# rs485_interface.net
KiCad netlist of a schematic drawn in EAGLE
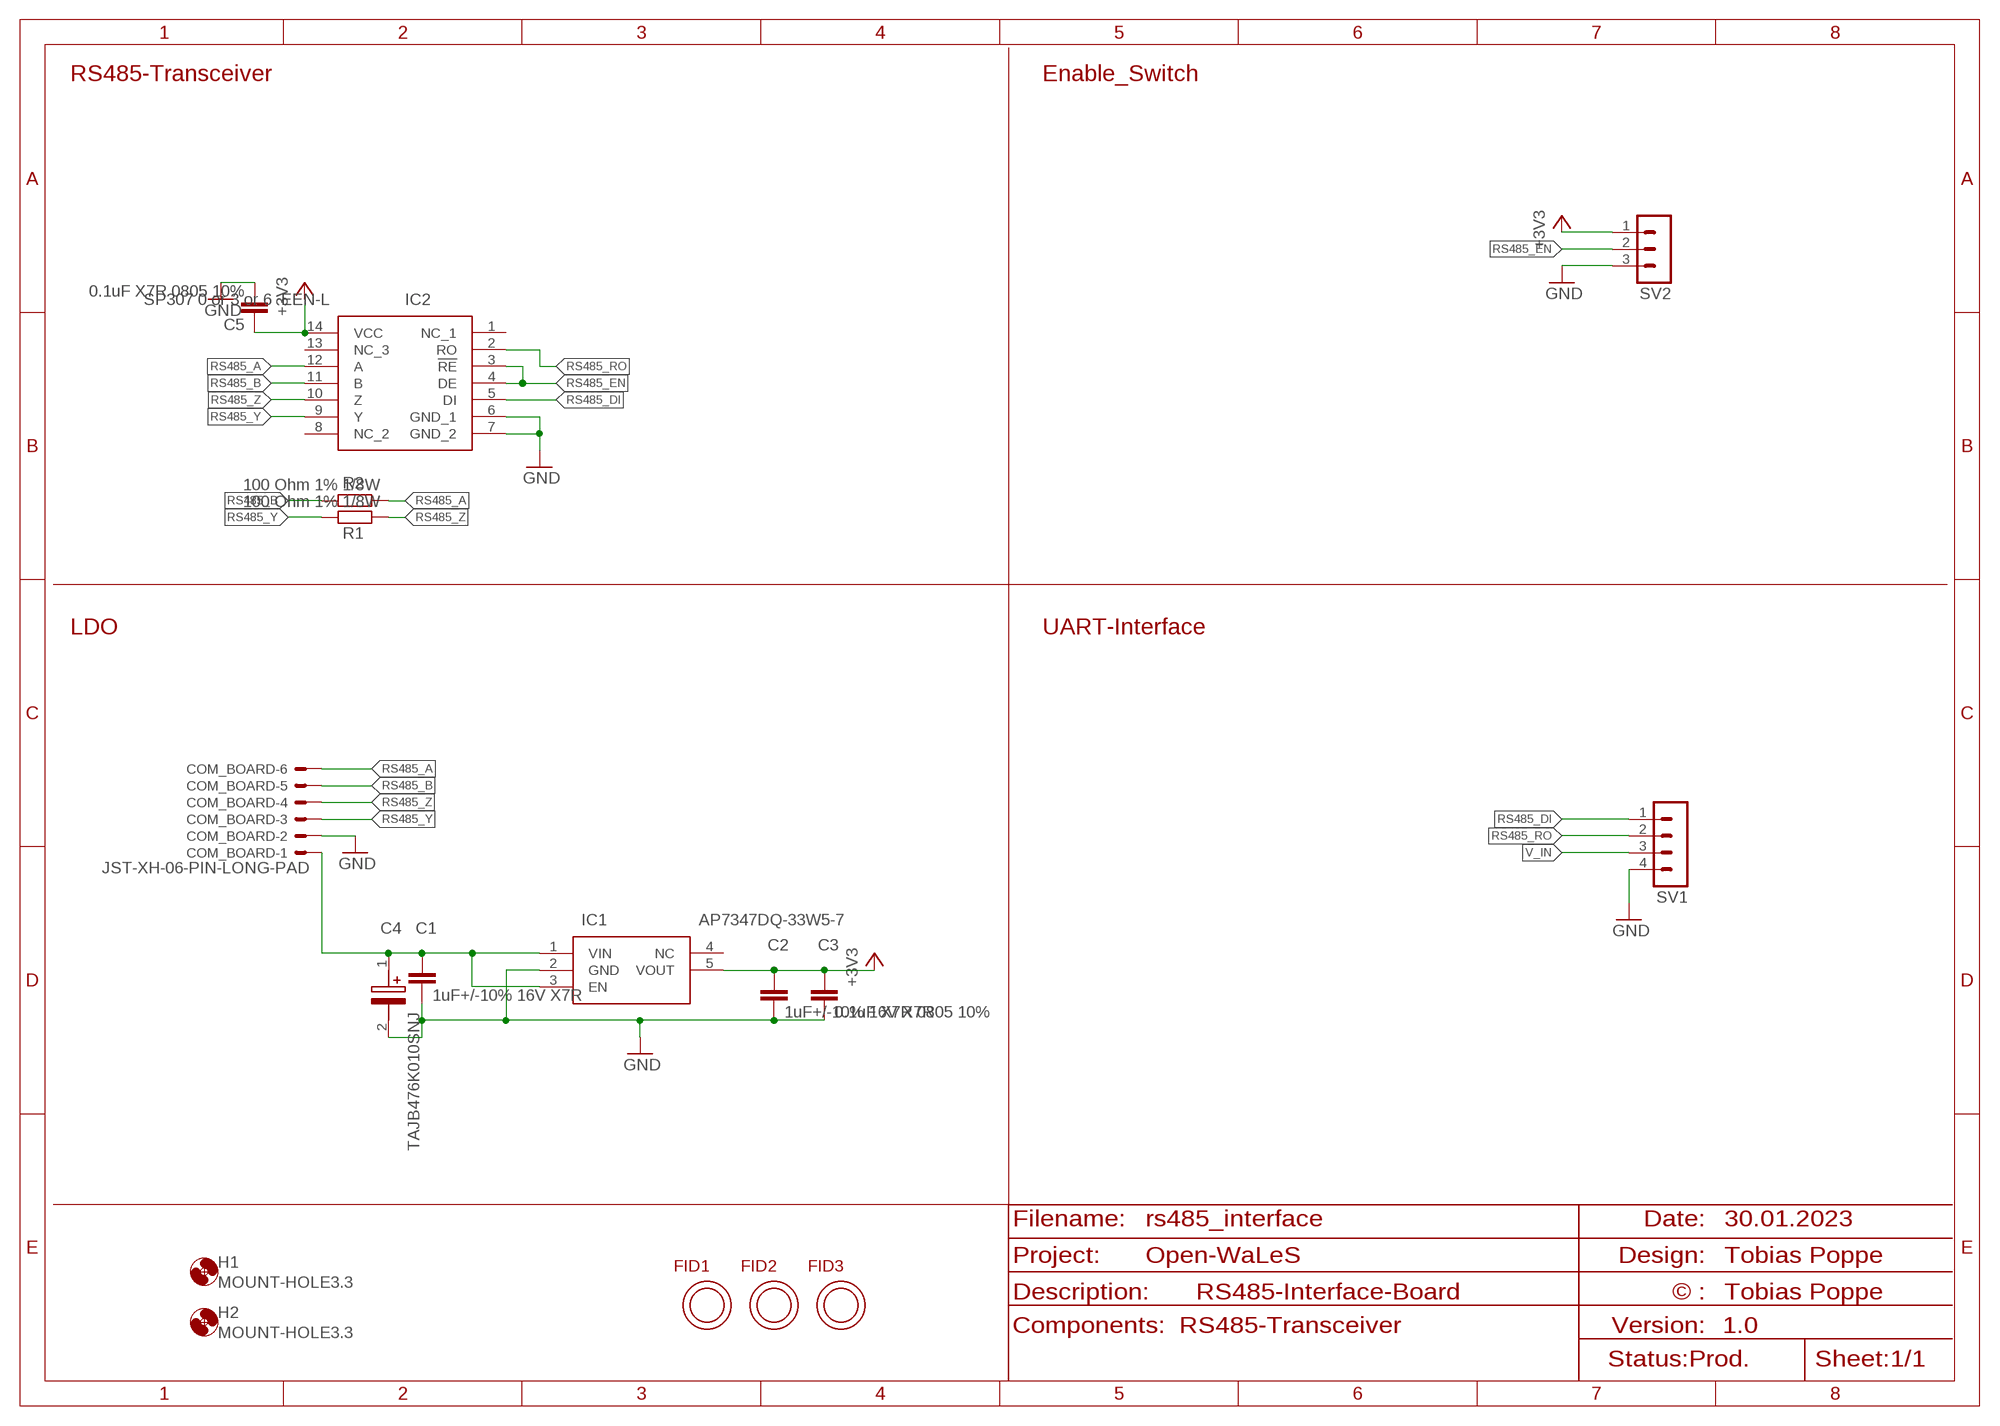
[diagram p0: schematic, sheet 1]

(export (version "E")
  (design (tool "Eeschema 10.0.6"))
  (components
    (comp (ref "C1")
      (value "1uF+/-10% 16V X7R")
      (footprint "eagle-import:C0805")
      (libsource (lib "eagle-import") (part "C-EUC0805"))
    )
    (comp (ref "C2")
      (value "1uF+/-10% 16V X7R")
      (footprint "eagle-import:C0805")
      (libsource (lib "eagle-import") (part "C-EUC0805"))
    )
    (comp (ref "C3")
      (value "0.1uF X7R 0805 10%")
      (footprint "eagle-import:C0805")
      (libsource (lib "eagle-import") (part "C-EUC0805"))
    )
    (comp (ref "C4")
      (value "TAJB476K010SNJ")
      (footprint "eagle-import:CAPPM3528X210N")
      (fields (field (name "MOUSER_PART_NUMBER") "581-TAJB476K010SNJ"))
      (libsource (lib "eagle-import") (part "TAJB476K010SNJ"))
    )
    (comp (ref "C5")
      (value "0.1uF X7R 0805 10%")
      (footprint "eagle-import:C0805")
      (libsource (lib "eagle-import") (part "C-EUC0805"))
    )
    (comp (ref "COM_BOARD")
      (value "JST-XH-06-PIN-LONG-PAD")
      (footprint "eagle-import:JST-XH-06-PACKAGE-LONG-PAD")
      (libsource (lib "eagle-import") (part "JST-XH-06-PIN-LONG-PAD"))
    )
    (comp (ref "FID1")
      (value "OPEN-PNP-FIDUCIAL")
      (footprint "eagle-import:OPEN-PNP-FIDUCIAL")
      (libsource (lib "eagle-import") (part "OPEN-PNP-FIDUCIAL"))
    )
    (comp (ref "FID2")
      (value "OPEN-PNP-FIDUCIAL")
      (footprint "eagle-import:OPEN-PNP-FIDUCIAL")
      (libsource (lib "eagle-import") (part "OPEN-PNP-FIDUCIAL"))
    )
    (comp (ref "FID3")
      (value "OPEN-PNP-FIDUCIAL")
      (footprint "eagle-import:OPEN-PNP-FIDUCIAL")
      (libsource (lib "eagle-import") (part "OPEN-PNP-FIDUCIAL"))
    )
    (comp (ref "H1")
      (value "MOUNT-HOLE3.3")
      (footprint "eagle-import:3,3")
      (libsource (lib "eagle-import") (part "MOUNT-HOLE3.3"))
    )
    (comp (ref "H2")
      (value "MOUNT-HOLE3.3")
      (footprint "eagle-import:3,3")
      (libsource (lib "eagle-import") (part "MOUNT-HOLE3.3"))
    )
    (comp (ref "IC1")
      (value "AP7347DQ-33W5-7")
      (footprint "eagle-import:SOT95P280X145-5N")
      (fields (field (name "MOUSER_PART_NUMBER") "621-AP7347DQ-33W5-7"))
      (libsource (lib "eagle-import") (part "AP7347DQ-33W5-7"))
    )
    (comp (ref "IC2")
      (value "SP307 0 or 3 or 6 EEN-L")
      (footprint "eagle-import:SOIC127P600X175-14N")
      (fields
        (field (name "MANUFACTURER_PART_NUMBER") "SP3076EEN-L")
        (field (name "MOUSER_PART_NUMBER") "701-SP3076EEN-L")
      )
      (libsource (lib "eagle-import") (part "SP3076EEN-L"))
    )
    (comp (ref "R1")
      (value "100 Ohm 1% 1/8W")
      (footprint "eagle-import:R0805")
      (libsource (lib "eagle-import") (part "R-EU_R0805"))
    )
    (comp (ref "R2")
      (value "100 Ohm 1% 1/8W")
      (footprint "eagle-import:R0805")
      (libsource (lib "eagle-import") (part "R-EU_R0805"))
    )
    (comp (ref "SV1")
      (value "MA04-1")
      (footprint "eagle-import:MA04-1")
      (libsource (lib "eagle-import") (part "MA04-1"))
    )
    (comp (ref "SV2")
      (value "MA03-1")
      (footprint "eagle-import:MA03-1")
      (libsource (lib "eagle-import") (part "MA03-1"))
    )
  )
  (nets
    (net (code "1") (name "+3V3") (class "Default")
      (node (ref "C2") (pin "1") (pinfunction "1_1") (pintype "passive"))
      (node (ref "C3") (pin "1") (pinfunction "1_1") (pintype "passive"))
      (node (ref "C5") (pin "1") (pinfunction "1_1") (pintype "passive"))
      (node (ref "IC1") (pin "5") (pinfunction "VOUT_5") (pintype "bidirectional"))
      (node (ref "IC2") (pin "14") (pinfunction "VCC_14") (pintype "bidirectional"))
      (node (ref "SV2") (pin "1") (pinfunction "1_1") (pintype "passive"))
    )
    (net (code "2") (name "GND") (class "Default")
      (node (ref "C1") (pin "2") (pinfunction "2_2") (pintype "passive"))
      (node (ref "C2") (pin "2") (pinfunction "2_2") (pintype "passive"))
      (node (ref "C3") (pin "2") (pinfunction "2_2") (pintype "passive"))
      (node (ref "C4") (pin "2") (pinfunction "-_2") (pintype "bidirectional"))
      (node (ref "C5") (pin "2") (pinfunction "2_2") (pintype "passive"))
      (node (ref "COM_BOARD") (pin "2") (pinfunction "S_2") (pintype "passive"))
      (node (ref "IC1") (pin "2") (pinfunction "GND_2") (pintype "bidirectional"))
      (node (ref "IC2") (pin "6") (pinfunction "GND_1_6") (pintype "bidirectional"))
      (node (ref "IC2") (pin "7") (pinfunction "GND_2_7") (pintype "bidirectional"))
      (node (ref "SV1") (pin "4") (pinfunction "4_4") (pintype "passive"))
      (node (ref "SV2") (pin "3") (pinfunction "3_3") (pintype "passive"))
    )
    (net (code "3") (name "RS485_A") (class "Default")
      (node (ref "COM_BOARD") (pin "6") (pinfunction "S_6") (pintype "passive"))
      (node (ref "IC2") (pin "12") (pinfunction "A_12") (pintype "bidirectional"))
      (node (ref "R2") (pin "1") (pinfunction "1_1") (pintype "passive"))
    )
    (net (code "4") (name "RS485_B") (class "Default")
      (node (ref "COM_BOARD") (pin "5") (pinfunction "S_5") (pintype "passive"))
      (node (ref "IC2") (pin "11") (pinfunction "B_11") (pintype "bidirectional"))
      (node (ref "R2") (pin "2") (pinfunction "2_2") (pintype "passive"))
    )
    (net (code "5") (name "RS485_DI") (class "Default")
      (node (ref "IC2") (pin "5") (pinfunction "DI_5") (pintype "bidirectional"))
      (node (ref "SV1") (pin "1") (pinfunction "1_1") (pintype "passive"))
    )
    (net (code "6") (name "RS485_EN") (class "Default")
      (node (ref "IC2") (pin "3") (pinfunction "~{RE}_3") (pintype "bidirectional"))
      (node (ref "IC2") (pin "4") (pinfunction "DE_4") (pintype "bidirectional"))
      (node (ref "SV2") (pin "2") (pinfunction "2_2") (pintype "passive"))
    )
    (net (code "7") (name "RS485_RO") (class "Default")
      (node (ref "IC2") (pin "2") (pinfunction "RO_2") (pintype "bidirectional"))
      (node (ref "SV1") (pin "2") (pinfunction "2_2") (pintype "passive"))
    )
    (net (code "8") (name "RS485_Y") (class "Default")
      (node (ref "COM_BOARD") (pin "3") (pinfunction "S_3") (pintype "passive"))
      (node (ref "IC2") (pin "9") (pinfunction "Y_9") (pintype "bidirectional"))
      (node (ref "R1") (pin "2") (pinfunction "2_2") (pintype "passive"))
    )
    (net (code "9") (name "RS485_Z") (class "Default")
      (node (ref "COM_BOARD") (pin "4") (pinfunction "S_4") (pintype "passive"))
      (node (ref "IC2") (pin "10") (pinfunction "Z_10") (pintype "bidirectional"))
      (node (ref "R1") (pin "1") (pinfunction "1_1") (pintype "passive"))
    )
    (net (code "10") (name "V_IN") (class "Default")
      (node (ref "C1") (pin "1") (pinfunction "1_1") (pintype "passive"))
      (node (ref "C4") (pin "1") (pinfunction "+_1") (pintype "bidirectional"))
      (node (ref "COM_BOARD") (pin "1") (pinfunction "S_1") (pintype "passive"))
      (node (ref "IC1") (pin "1") (pinfunction "VIN_1") (pintype "bidirectional"))
      (node (ref "IC1") (pin "3") (pinfunction "EN_3") (pintype "bidirectional"))
      (node (ref "SV1") (pin "3") (pinfunction "3_3") (pintype "passive"))
    )
    (net (code "11") (name "unconnected-(IC1-NC-Pad4)") (class "Default")
      (node (ref "IC1") (pin "4") (pinfunction "NC_4") (pintype "no_connect"))
    )
    (net (code "12") (name "unconnected-(IC2-NC_1-Pad1)") (class "Default")
      (node (ref "IC2") (pin "1") (pinfunction "NC_1_1") (pintype "bidirectional"))
    )
    (net (code "13") (name "unconnected-(IC2-NC_2-Pad8)") (class "Default")
      (node (ref "IC2") (pin "8") (pinfunction "NC_2_8") (pintype "bidirectional"))
    )
    (net (code "14") (name "unconnected-(IC2-NC_3-Pad13)") (class "Default")
      (node (ref "IC2") (pin "13") (pinfunction "NC_3_13") (pintype "bidirectional"))
    )
  )
)
